# emulator_reve.net
KiCad netlist of a schematic drawn in EAGLE
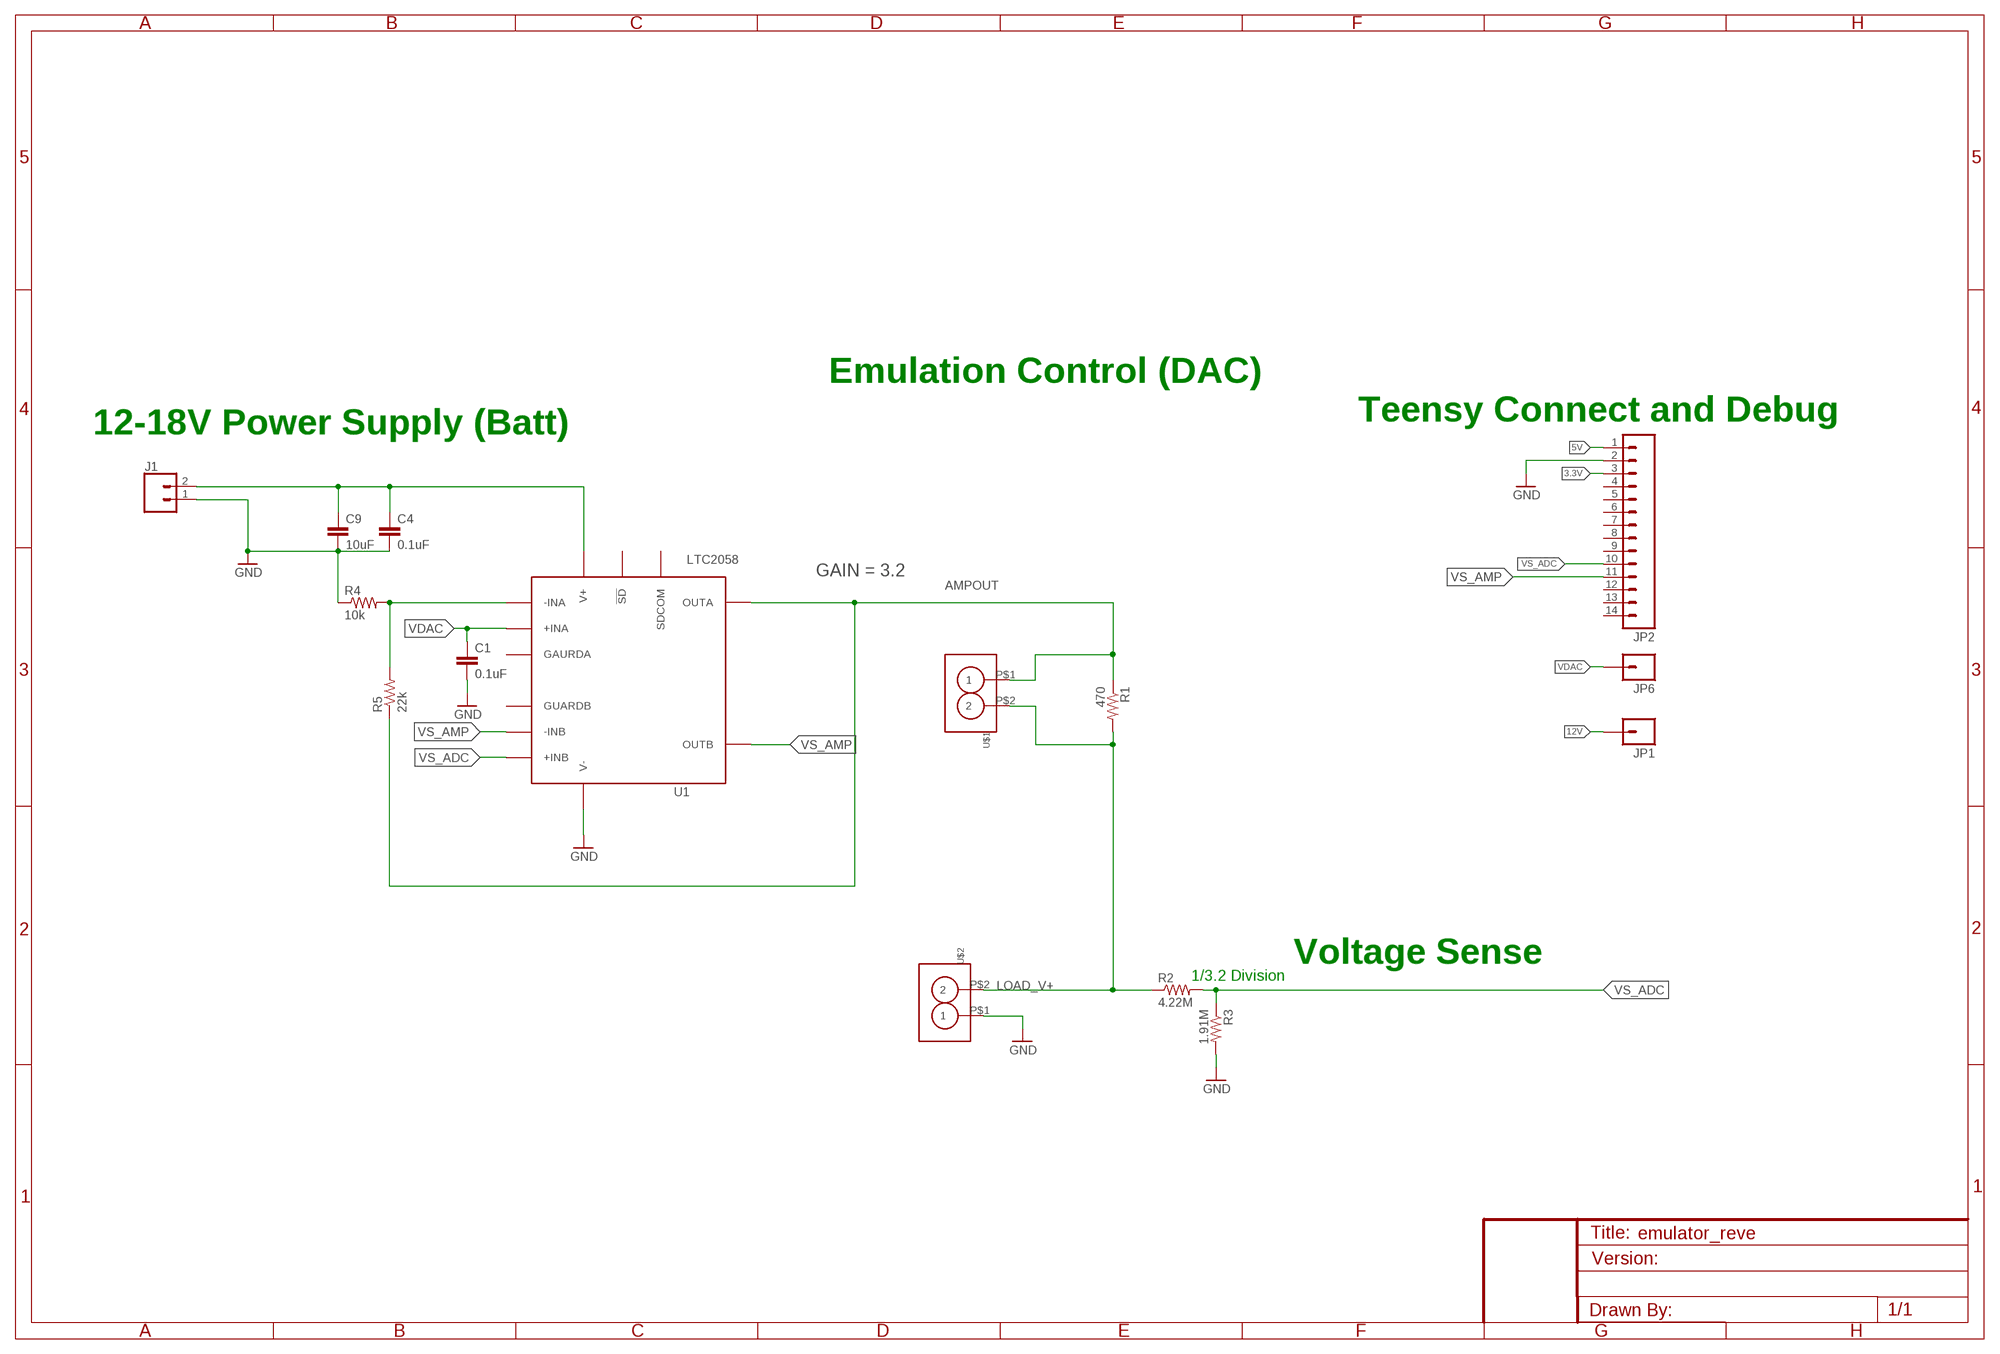
[diagram p0: schematic, sheet 1]

(export (version "E")
  (design (tool "Eeschema 10.0.6"))
  (components
    (comp (ref "C1")
      (value "0.1uF")
      (footprint "eagle-import:0603")
      (libsource (lib "eagle-import") (part "C-EU0603"))
    )
    (comp (ref "C4")
      (value "0.1uF")
      (footprint "eagle-import:0603")
      (libsource (lib "eagle-import") (part "C-EU0603"))
    )
    (comp (ref "C9")
      (value "10uF")
      (footprint "eagle-import:1210")
      (libsource (lib "eagle-import") (part "CAP1210"))
    )
    (comp (ref "J1")
      (value "CONN_02")
      (footprint "eagle-import:1X02")
      (libsource (lib "eagle-import") (part "CONN_02"))
    )
    (comp (ref "JP1")
      (value "M01PTH")
      (footprint "eagle-import:1X01")
      (libsource (lib "eagle-import") (part "M01PTH"))
    )
    (comp (ref "JP2")
      (value "M14")
      (footprint "eagle-import:1X14")
      (libsource (lib "eagle-import") (part "M14"))
    )
    (comp (ref "JP6")
      (value "M01PTH")
      (footprint "eagle-import:1X01")
      (libsource (lib "eagle-import") (part "M01PTH"))
    )
    (comp (ref "R1")
      (value "470")
      (footprint "eagle-import:0805")
      (libsource (lib "eagle-import") (part "RESISTOR0805-RES"))
    )
    (comp (ref "R2")
      (value "4.22M")
      (footprint "eagle-import:0603")
      (libsource (lib "eagle-import") (part "R-EU0603"))
    )
    (comp (ref "R3")
      (value "1.91M")
      (footprint "eagle-import:0603")
      (libsource (lib "eagle-import") (part "R-EU0603"))
    )
    (comp (ref "R4")
      (value "10k")
      (footprint "eagle-import:0603")
      (libsource (lib "eagle-import") (part "R-EU0603"))
    )
    (comp (ref "R5")
      (value "22k")
      (footprint "eagle-import:0603")
      (libsource (lib "eagle-import") (part "R-EU0603"))
    )
    (comp (ref "U$1")
      (value "SCREW_CONNECTOR-2PIN'")
      (footprint "eagle-import:SCREW_CONNECTOR-2PIN-3.5MM")
      (libsource (lib "eagle-import") (part "SCREW_CONNECTOR-2PIN'"))
    )
    (comp (ref "U$2")
      (value "SCREW_CONNECTOR-2PIN'")
      (footprint "eagle-import:SCREW_CONNECTOR-2PIN-3.5MM")
      (libsource (lib "eagle-import") (part "SCREW_CONNECTOR-2PIN'"))
    )
    (comp (ref "U1")
      (value "LTC2058")
      (footprint "eagle-import:MSOP12")
      (libsource (lib "eagle-import") (part "LTC2058"))
    )
  )
  (nets
    (net (code "1") (name "/AMPOUT") (class "Default")
      (node (ref "R1") (pin "1") (pinfunction "1_1") (pintype "passive"))
      (node (ref "R5") (pin "1") (pinfunction "1_1") (pintype "passive"))
      (node (ref "U$1") (pin "P$1") (pinfunction "1_P$1") (pintype "bidirectional"))
      (node (ref "U1") (pin "3") (pinfunction "OUTA_3") (pintype "bidirectional"))
    )
    (net (code "2") (name "/LOAD_V+") (class "Default")
      (node (ref "R1") (pin "2") (pinfunction "2_2") (pintype "passive"))
      (node (ref "R2") (pin "1") (pinfunction "1_1") (pintype "passive"))
      (node (ref "U$1") (pin "P$2") (pinfunction "2_P$2") (pintype "bidirectional"))
      (node (ref "U$2") (pin "P$2") (pinfunction "2_P$2") (pintype "bidirectional"))
    )
    (net (code "3") (name "3.3V") (class "Default")
      (node (ref "JP2") (pin "3") (pinfunction "3_3") (pintype "passive"))
    )
    (net (code "4") (name "5V") (class "Default")
      (node (ref "JP2") (pin "1") (pinfunction "1_1") (pintype "passive"))
    )
    (net (code "5") (name "12V") (class "Default")
      (node (ref "C4") (pin "1") (pinfunction "1_1") (pintype "passive"))
      (node (ref "C9") (pin "1") (pinfunction "1_1") (pintype "passive"))
      (node (ref "J1") (pin "2") (pinfunction "2_2") (pintype "passive"))
      (node (ref "JP1") (pin "1") (pinfunction "1_1") (pintype "passive"))
      (node (ref "U1") (pin "11") (pinfunction "V+_11") (pintype "power_in"))
    )
    (net (code "6") (name "GND") (class "Default")
      (node (ref "C1") (pin "2") (pinfunction "2_2") (pintype "passive"))
      (node (ref "C4") (pin "2") (pinfunction "2_2") (pintype "passive"))
      (node (ref "C9") (pin "2") (pinfunction "2_2") (pintype "passive"))
      (node (ref "J1") (pin "1") (pinfunction "1_1") (pintype "passive"))
      (node (ref "JP2") (pin "2") (pinfunction "2_2") (pintype "passive"))
      (node (ref "R3") (pin "2") (pinfunction "2_2") (pintype "passive"))
      (node (ref "R4") (pin "1") (pinfunction "1_1") (pintype "passive"))
      (node (ref "U$2") (pin "P$1") (pinfunction "1_P$1") (pintype "bidirectional"))
      (node (ref "U1") (pin "2") (pinfunction "V-_2") (pintype "power_in"))
      (node (ref "U1") (pin "EXP") (pinfunction "V-_EXP") (pintype "power_in"))
    )
    (net (code "7") (name "Net-(U1--INA)") (class "Default")
      (node (ref "R4") (pin "2") (pinfunction "2_2") (pintype "passive"))
      (node (ref "R5") (pin "2") (pinfunction "2_2") (pintype "passive"))
      (node (ref "U1") (pin "5") (pinfunction "-INA_5") (pintype "bidirectional"))
    )
    (net (code "8") (name "VDAC") (class "Default")
      (node (ref "C1") (pin "1") (pinfunction "1_1") (pintype "passive"))
      (node (ref "JP6") (pin "1") (pinfunction "1_1") (pintype "passive"))
      (node (ref "U1") (pin "6") (pinfunction "+INA_6") (pintype "bidirectional"))
    )
    (net (code "9") (name "VS_ADC") (class "Default")
      (node (ref "JP2") (pin "10") (pinfunction "10_10") (pintype "passive"))
      (node (ref "R2") (pin "2") (pinfunction "2_2") (pintype "passive"))
      (node (ref "R3") (pin "1") (pinfunction "1_1") (pintype "passive"))
      (node (ref "U1") (pin "7") (pinfunction "+INB_7") (pintype "bidirectional"))
    )
    (net (code "10") (name "VS_AMP") (class "Default")
      (node (ref "JP2") (pin "11") (pinfunction "11_11") (pintype "passive"))
      (node (ref "U1") (pin "10") (pinfunction "OUTB_10") (pintype "bidirectional"))
      (node (ref "U1") (pin "8") (pinfunction "-INB_8") (pintype "bidirectional"))
    )
    (net (code "11") (name "unconnected-(JP2-Pad4)") (class "Default")
      (node (ref "JP2") (pin "4") (pinfunction "4_4") (pintype "passive"))
    )
    (net (code "12") (name "unconnected-(JP2-Pad5)") (class "Default")
      (node (ref "JP2") (pin "5") (pinfunction "5_5") (pintype "passive"))
    )
    (net (code "13") (name "unconnected-(JP2-Pad6)") (class "Default")
      (node (ref "JP2") (pin "6") (pinfunction "6_6") (pintype "passive"))
    )
    (net (code "14") (name "unconnected-(JP2-Pad7)") (class "Default")
      (node (ref "JP2") (pin "7") (pinfunction "7_7") (pintype "passive"))
    )
    (net (code "15") (name "unconnected-(JP2-Pad8)") (class "Default")
      (node (ref "JP2") (pin "8") (pinfunction "8_8") (pintype "passive"))
    )
    (net (code "16") (name "unconnected-(JP2-Pad9)") (class "Default")
      (node (ref "JP2") (pin "9") (pinfunction "9_9") (pintype "passive"))
    )
    (net (code "17") (name "unconnected-(JP2-Pad12)") (class "Default")
      (node (ref "JP2") (pin "12") (pinfunction "12_12") (pintype "passive"))
    )
    (net (code "18") (name "unconnected-(JP2-Pad13)") (class "Default")
      (node (ref "JP2") (pin "13") (pinfunction "13_13") (pintype "passive"))
    )
    (net (code "19") (name "unconnected-(JP2-Pad14)") (class "Default")
      (node (ref "JP2") (pin "14") (pinfunction "14_14") (pintype "passive"))
    )
    (net (code "20") (name "unconnected-(U1-GAURDA-Pad4)") (class "Default")
      (node (ref "U1") (pin "4") (pinfunction "GAURDA_4") (pintype "bidirectional"))
    )
    (net (code "21") (name "unconnected-(U1-GUARDB-Pad9)") (class "Default")
      (node (ref "U1") (pin "9") (pinfunction "GUARDB_9") (pintype "bidirectional"))
    )
    (net (code "22") (name "unconnected-(U1-SDCOM-Pad12)") (class "Default")
      (node (ref "U1") (pin "12") (pinfunction "SDCOM_12") (pintype "bidirectional"))
    )
    (net (code "23") (name "unconnected-(U1-~{SD}-Pad1)") (class "Default")
      (node (ref "U1") (pin "1") (pinfunction "~{SD}_1") (pintype "bidirectional"))
    )
  )
)
